# High_Side_Driver.net
KiCad netlist of a schematic drawn in Altium Designer
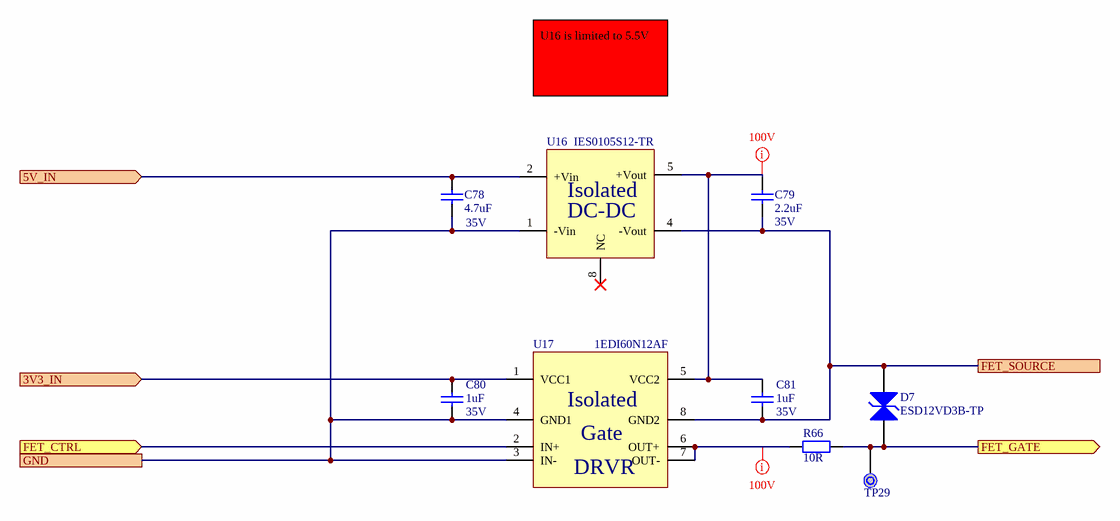
[diagram p0: High Side Driver.SchDoc]

(export (version "E")
  (design (tool "Eeschema 10.0.6"))
  (components
    (comp (ref "C78")
      (value "4.7uF")
      (footprint "0805 CAP")
      (description "Capacitor 4.7uF 0805 X7R 35V 10%")
      (fields (field (name "VOLTAGE") "35V"))
      (libsource (lib "Supernova Capacitors") (part "Capacitor 4.7uF 0805"))
    )
    (comp (ref "C79")
      (value "2.2uF")
      (footprint "0603 CAP")
      (description "Capacitor 2.2uF 0603 X5R 35V 10%")
      (fields (field (name "VOLTAGE") "35V"))
      (libsource (lib "Supernova Capacitors") (part "Capacitor 2.2uF 0603 35V"))
    )
    (comp (ref "C80")
      (value "1uF")
      (footprint "0603 CAP")
      (description "Capacitor 1uF 0603 X7R 35V 10%")
      (fields (field (name "VOLTAGE") "35V"))
      (libsource (lib "Supernova Capacitors") (part "Capacitor 1uF 0603"))
    )
    (comp (ref "C81")
      (value "1uF")
      (footprint "0603 CAP")
      (description "Capacitor 1uF 0603 X7R 35V 10%")
      (fields (field (name "VOLTAGE") "35V"))
      (libsource (lib "Supernova Capacitors") (part "Capacitor 1uF 0603"))
    )
    (comp (ref "D7")
      (value "ESD12VD3B-TP")
      (footprint "SOD323")
      (description "Diode 12V TVS")
      (libsource (lib "Supernova Diodes") (part "ESD12VD3B-TP"))
    )
    (comp (ref "R66")
      (value "10R")
      (footprint "0603 RES")
      (description "Resistor 10R 0603 0.1W 1%")
      (libsource (lib "Supernova Resistors") (part "Resistor 10R 0603"))
    )
    (comp (ref "TP29")
      (value "Testpoint SMD")
      (footprint "Testpoint - SMD")
      (libsource (lib "Supernova Connectors") (part "Testpoint SMD"))
    )
    (comp (ref "U16")
      (value "IES0105S12-TR")
      (footprint "SMD8")
      (description "Isolated DC/DC Converters DC-DC, 1W")
      (fields (field (name "MP") "HCPL2630S"))
      (libsource (lib "Asteria") (part "IES0105S12-TR"))
    )
    (comp (ref "U17")
      (value "1EDI60N12AF")
      (footprint "SOIC127-8")
      (description "Isolated Gate Driver")
      (fields (field (name "MOUSER2 PART NUMBER") "726-1EDI60N12AF"))
      (libsource (lib "Asteria") (part "1EDI60N12AF"))
    )
  )
  (nets
    (net (code "1") (name "/3V3_IN") (class "Default")
      (node (ref "C80") (pin "2") (pinfunction "2_2") (pintype "passive"))
      (node (ref "U17") (pin "1") (pinfunction "VCC1_1") (pintype "passive"))
    )
    (net (code "2") (name "/5V_IN") (class "Default")
      (node (ref "C78") (pin "2") (pinfunction "2_2") (pintype "passive"))
      (node (ref "U16") (pin "2") (pinfunction "+Vin_2") (pintype "passive"))
    )
    (net (code "3") (name "/FET_CTRL") (class "Default")
      (node (ref "U17") (pin "2") (pinfunction "IN+_2") (pintype "passive"))
    )
    (net (code "4") (name "/FET_GATE") (class "Default")
      (node (ref "D7") (pin "2") (pinfunction "A_2") (pintype "passive"))
      (node (ref "R66") (pin "1") (pinfunction "1_1") (pintype "passive"))
      (node (ref "TP29") (pin "1") (pinfunction "1_1") (pintype "passive"))
    )
    (net (code "5") (name "/FET_SOURCE") (class "Default")
      (node (ref "C79") (pin "2") (pinfunction "2_2") (pintype "passive"))
      (node (ref "C81") (pin "1") (pinfunction "1_1") (pintype "passive"))
      (node (ref "D7") (pin "1") (pinfunction "K_1") (pintype "passive"))
      (node (ref "U16") (pin "4") (pinfunction "-Vout_4") (pintype "passive"))
      (node (ref "U17") (pin "8") (pinfunction "GND2_8") (pintype "passive"))
    )
    (net (code "6") (name "/GND") (class "Default")
      (node (ref "C78") (pin "1") (pinfunction "1_1") (pintype "passive"))
      (node (ref "C80") (pin "1") (pinfunction "1_1") (pintype "passive"))
      (node (ref "U16") (pin "1") (pinfunction "-Vin_1") (pintype "passive"))
      (node (ref "U17") (pin "3") (pinfunction "IN-_3") (pintype "passive"))
      (node (ref "U17") (pin "4") (pinfunction "GND1_4") (pintype "passive"))
    )
    (net (code "7") (name "Net-(U16-+Vout)") (class "Default")
      (node (ref "C79") (pin "1") (pinfunction "1_1") (pintype "passive"))
      (node (ref "C81") (pin "2") (pinfunction "2_2") (pintype "passive"))
      (node (ref "U16") (pin "5") (pinfunction "+Vout_5") (pintype "passive"))
      (node (ref "U17") (pin "5") (pinfunction "VCC2_5") (pintype "passive"))
    )
    (net (code "8") (name "Net-(U17-OUT+)") (class "Default")
      (node (ref "R66") (pin "2") (pinfunction "2_2") (pintype "passive"))
      (node (ref "U17") (pin "6") (pinfunction "OUT+_6") (pintype "passive"))
      (node (ref "U17") (pin "7") (pinfunction "OUT-_7") (pintype "passive"))
    )
    (net (code "9") (name "unconnected-(U16-NC-Pad8)") (class "Default")
      (node (ref "U16") (pin "8") (pinfunction "NC_8") (pintype "passive+no_connect"))
    )
  )
)
